# iot_hdmi_mux.net
KiCad netlist of a schematic drawn in Altium Designer
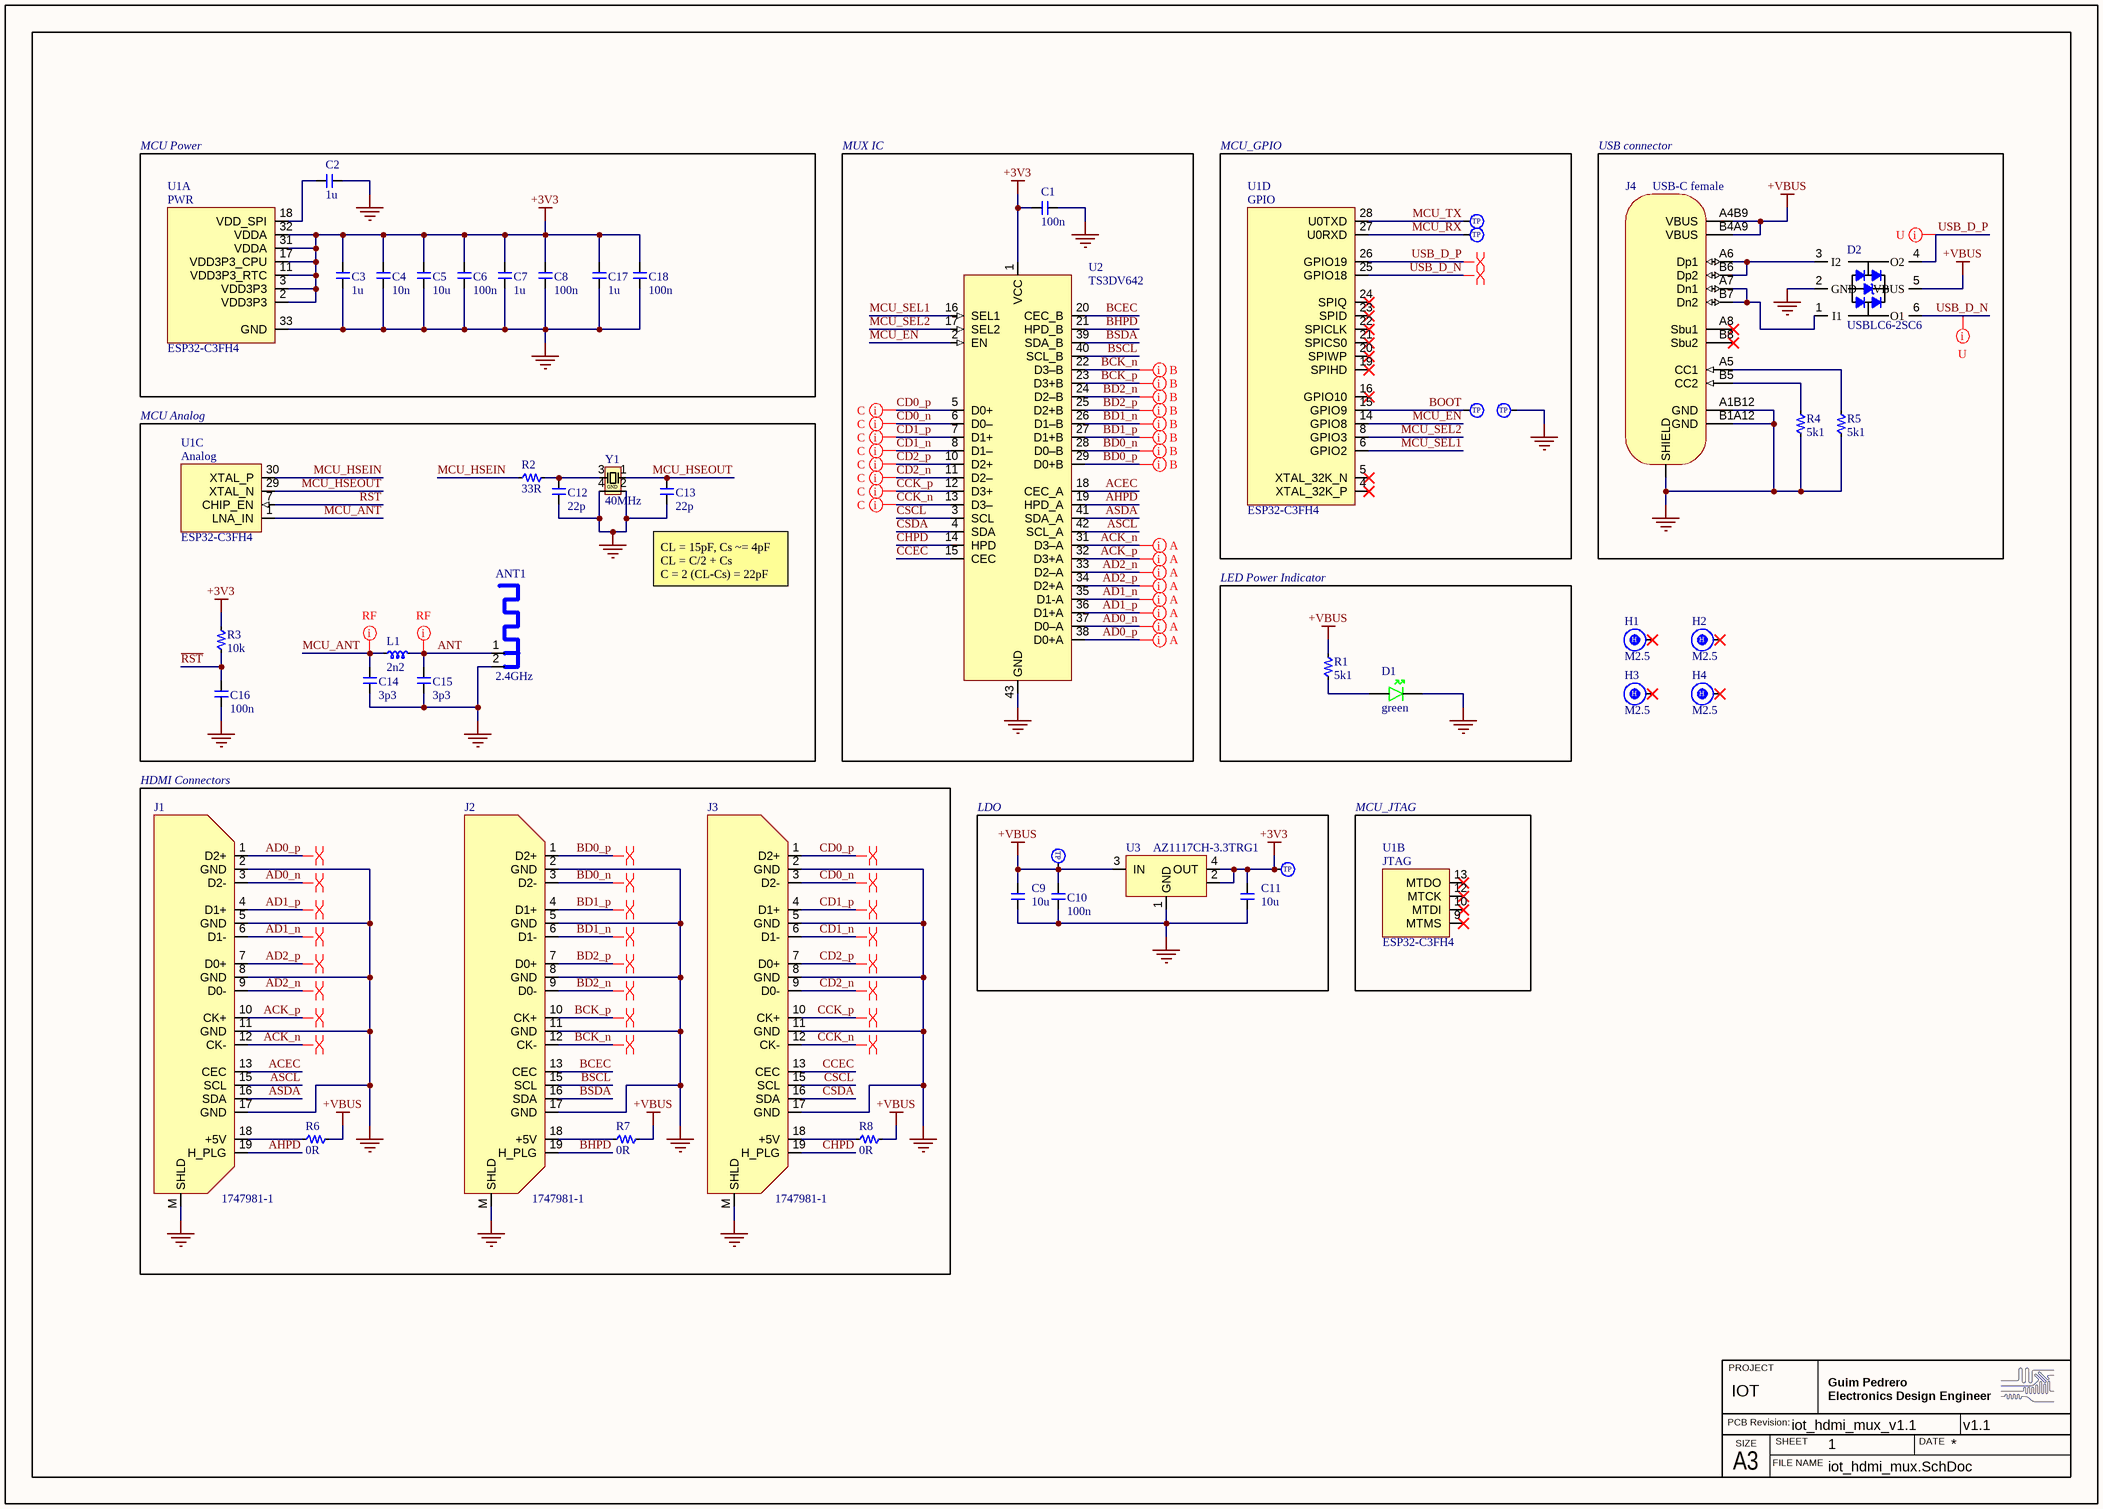
[diagram p0: iot_hdmi_mux.SchDoc]

(export (version "E")
  (design (tool "Eeschema 10.0.6"))
  (components
    (comp (ref "ANT1")
      (value "2.4GHz")
      (footprint "ANT_2.4")
      (description "SWRA117D 2.4GHz antenna design by TI")
      (libsource (lib "iot_hdmi_mux") (part "ANT_2.4"))
    )
    (comp (ref "C1")
      (value "100n")
      (footprint "C0402")
      (description "0402 cap")
      (libsource (lib "iot_hdmi_mux") (part "C_0402"))
    )
    (comp (ref "C2")
      (value "1u")
      (footprint "C0402")
      (description "0402 cap")
      (libsource (lib "LinearDriver") (part "C_0402"))
    )
    (comp (ref "C3")
      (value "1u")
      (footprint "C0402")
      (description "0402 cap")
      (libsource (lib "LinearDriver") (part "C_0402"))
    )
    (comp (ref "C4")
      (value "10n")
      (footprint "C0402")
      (description "0402 cap")
      (libsource (lib "iot_hdmi_mux") (part "C_0402"))
    )
    (comp (ref "C5")
      (value "10u")
      (footprint "C0402")
      (description "0402 cap")
      (libsource (lib "LinearDriver") (part "C_0402"))
    )
    (comp (ref "C6")
      (value "100n")
      (footprint "C0402")
      (description "0402 cap")
      (libsource (lib "iot_hdmi_mux") (part "C_0402"))
    )
    (comp (ref "C7")
      (value "1u")
      (footprint "C0402")
      (description "0402 cap")
      (libsource (lib "LinearDriver") (part "C_0402"))
    )
    (comp (ref "C8")
      (value "100n")
      (footprint "C0402")
      (description "0402 cap")
      (libsource (lib "iot_hdmi_mux") (part "C_0402"))
    )
    (comp (ref "C9")
      (value "10u")
      (footprint "C0402")
      (description "0402 cap")
      (libsource (lib "LinearDriver") (part "C_0402"))
    )
    (comp (ref "C10")
      (value "100n")
      (footprint "C0402")
      (description "0402 cap")
      (libsource (lib "iot_hdmi_mux") (part "C_0402"))
    )
    (comp (ref "C11")
      (value "10u")
      (footprint "C0402")
      (description "0402 cap")
      (libsource (lib "LinearDriver") (part "C_0402"))
    )
    (comp (ref "C12")
      (value "22p")
      (footprint "C0402")
      (description "0402 cap")
      (libsource (lib "FOC_Drive") (part "C_0402"))
    )
    (comp (ref "C13")
      (value "22p")
      (footprint "C0402")
      (description "0402 cap")
      (libsource (lib "FOC_Drive") (part "C_0402"))
    )
    (comp (ref "C14")
      (value "3p3")
      (footprint "C0402")
      (description "0402 cap")
      (libsource (lib "iot_hdmi_mux") (part "C_0402"))
    )
    (comp (ref "C15")
      (value "3p3")
      (footprint "C0402")
      (description "0402 cap")
      (libsource (lib "iot_hdmi_mux") (part "C_0402"))
    )
    (comp (ref "C16")
      (value "100n")
      (footprint "C0402")
      (description "0402 cap")
      (libsource (lib "iot_hdmi_mux") (part "C_0402"))
    )
    (comp (ref "C17")
      (value "1u")
      (footprint "C0402")
      (description "0402 cap")
      (libsource (lib "LinearDriver") (part "C_0402"))
    )
    (comp (ref "C18")
      (value "100n")
      (footprint "C0402")
      (description "0402 cap")
      (libsource (lib "iot_hdmi_mux") (part "C_0402"))
    )
    (comp (ref "D1")
      (value "green")
      (footprint "LED_0805_G")
      (description "0805 green LED")
      (libsource (lib "iot_hdmi_mux") (part "LED_0805_G"))
    )
    (comp (ref "D2")
      (value "USBLC6-2SC6")
      (footprint "USBLC6-2SC6")
      (description "Trans Voltage Suppressor Diode, 5V V(RWM), Unidirectional, 1 Element, Silicon")
      (fields (field (name "MANUFACTURER") "STMicroelectronics"))
      (libsource (lib "R20_PCBM") (part "USBLC6-2SC6"))
    )
    (comp (ref "H1")
      (value "M2.5")
      (footprint "M2.5_HOLE")
      (description "M2.5 hole with connection")
      (libsource (lib "iot_hdmi_mux") (part "M2.5_HOLE"))
    )
    (comp (ref "H2")
      (value "M2.5")
      (footprint "M2.5_HOLE")
      (description "M2.5 hole with connection")
      (libsource (lib "iot_hdmi_mux") (part "M2.5_HOLE"))
    )
    (comp (ref "H3")
      (value "M2.5")
      (footprint "M2.5_HOLE")
      (description "M2.5 hole with connection")
      (libsource (lib "iot_hdmi_mux") (part "M2.5_HOLE"))
    )
    (comp (ref "H4")
      (value "M2.5")
      (footprint "M2.5_HOLE")
      (description "M2.5 hole with connection")
      (libsource (lib "iot_hdmi_mux") (part "M2.5_HOLE"))
    )
    (comp (ref "J1")
      (value "1747981-1")
      (footprint "1747981-1")
      (description "HDMI (High-Definition Multimedia Interface) Connector; No Flange; Through hole")
      (fields (field (name "MANUFACTURER") "AMP - TE CONNECTIVITY"))
      (libsource (lib "iot_hdmi_mux") (part "1747981-1"))
    )
    (comp (ref "J2")
      (value "1747981-1")
      (footprint "1747981-1")
      (description "HDMI (High-Definition Multimedia Interface) Connector; No Flange; Through hole")
      (fields (field (name "MANUFACTURER") "AMP - TE CONNECTIVITY"))
      (libsource (lib "iot_hdmi_mux") (part "1747981-1"))
    )
    (comp (ref "J3")
      (value "1747981-1")
      (footprint "1747981-1")
      (description "HDMI (High-Definition Multimedia Interface) Connector; No Flange; Through hole")
      (fields (field (name "MANUFACTURER") "AMP - TE CONNECTIVITY"))
      (libsource (lib "iot_hdmi_mux") (part "1747981-1"))
    )
    (comp (ref "J4")
      (value "USB-C female")
      (footprint "TYPE-C-31-M-12")
      (description "Conn USB Type C PL 22 POS 0.5mm Solder ST SMD 22 Terminal 1Port Emboss T/R")
      (fields
        (field (name "MANUFACTURER") "HRO Electronics")
        (field (name "MANUFACTURER PART NUMBER") "TYPE-C-31-M-12")
      )
      (libsource (lib "rotor_magnetics_tb") (part "TYPE-C-31-M-12"))
    )
    (comp (ref "L1")
      (value "2n2")
      (footprint "L0402")
      (description "0402 inductor")
      (libsource (lib "iot_hdmi_mux") (part "L_0402"))
    )
    (comp (ref "R1")
      (value "5k1")
      (footprint "R0402")
      (description "0402 62.5mW")
      (libsource (lib "PCB_motor") (part "R_0402"))
    )
    (comp (ref "R2")
      (value "33R")
      (footprint "R0402")
      (description "0402 62.5mW")
      (libsource (lib "iot_hdmi_mux") (part "R_0402"))
    )
    (comp (ref "R3")
      (value "10k")
      (footprint "R0402")
      (description "0402 62.5mW")
      (libsource (lib "iot_hdmi_mux") (part "R_0402"))
    )
    (comp (ref "R4")
      (value "5k1")
      (footprint "R0402")
      (description "0402 62.5mW")
      (libsource (lib "PCB_motor") (part "R_0402"))
    )
    (comp (ref "R5")
      (value "5k1")
      (footprint "R0402")
      (description "0402 62.5mW")
      (libsource (lib "PCB_motor") (part "R_0402"))
    )
    (comp (ref "R6")
      (value "0R")
      (footprint "R0402")
      (description "0402 62.5mW")
      (libsource (lib "iot_hdmi_mux") (part "R_0402"))
    )
    (comp (ref "R7")
      (value "0R")
      (footprint "R0402")
      (description "0402 62.5mW")
      (libsource (lib "iot_hdmi_mux") (part "R_0402"))
    )
    (comp (ref "R8")
      (value "0R")
      (footprint "R0402")
      (description "0402 62.5mW")
      (libsource (lib "iot_hdmi_mux") (part "R_0402"))
    )
    (comp (ref "TP1")
      (value "Testing_Point_1mm")
      (footprint "TestingPoint_1mm")
      (description "1mm testing point")
      (libsource (lib "iot_hdmi_mux") (part "Testing_Point_1mm"))
    )
    (comp (ref "TP2")
      (value "Testing_Point_1mm")
      (footprint "TestingPoint_1mm")
      (description "1mm testing point")
      (libsource (lib "iot_hdmi_mux") (part "Testing_Point_1mm"))
    )
    (comp (ref "TP3")
      (value "Testing_Point_1mm")
      (footprint "TestingPoint_1mm")
      (description "1mm testing point")
      (libsource (lib "iot_hdmi_mux") (part "Testing_Point_1mm"))
    )
    (comp (ref "TP4")
      (value "Testing_Point_1mm")
      (footprint "TestingPoint_1mm")
      (description "1mm testing point")
      (libsource (lib "iot_hdmi_mux") (part "Testing_Point_1mm"))
    )
    (comp (ref "TP5")
      (value "Testing_Point_1mm")
      (footprint "TestingPoint_1mm")
      (description "1mm testing point")
      (libsource (lib "LinearDriver") (part "Testing_Point_1mm"))
    )
    (comp (ref "TP6")
      (value "Testing_Point_1mm")
      (footprint "TestingPoint_1mm")
      (description "1mm testing point")
      (libsource (lib "LinearDriver") (part "Testing_Point_1mm"))
    )
    (comp (ref "U1")
      (value "ESP32-C3FH4")
      (footprint "QFN50P500X500X90_HS-33N")
      (fields (field (name "MANUFACTURER") "Espressif Systems"))
      (libsource (lib "") (part "ESP32-C3FH4_1"))
    )
    (comp (ref "U2")
      (value "TS3DV642")
      (footprint "QFN50P350X900X80_HS-43N")
      (description "6-Gbps 12-channel differential 1-to-2 and 2-to-1 mux for DVI 1.0/ DisplayPort 1.4 /HDMI 2.0")
      (fields
        (field (name "MANUFACTURER") "Texas Instruments")
        (field (name "MANUFACTURER PART NUMBER") "TS3DV642A0RUAR")
      )
      (libsource (lib "iot_hdmi_mux") (part "TS3DV642"))
    )
    (comp (ref "U3")
      (value "AZ1117CH-3.3TRG1")
      (footprint "AZ1117CH-3.3TRG1")
      (description "Fixed Positive LDO Regulator, 3.3V, 1.3V Dropout, BIPolar, PDSO3")
      (fields (field (name "MANUFACTURER") "Diodes"))
      (libsource (lib "LinearDriver") (part "AZ1117CH-3.3TRG1"))
    )
    (comp (ref "Y1")
      (value "40MHz")
      (footprint "SMD3225-4P")
      (description "40MHz Surface Mount Crystal 15pF ±10ppm ±20ppm SMD3225-4P Crystals ROHS")
      (libsource (lib "iot_hdmi_mux") (part "X322540MPB4SI"))
    )
  )
  (nets
    (net (code "1") (name "+3V3") (class "Default")
      (node (ref "C1") (pin "2") (pinfunction "2_2") (pintype "passive"))
      (node (ref "C11") (pin "2") (pinfunction "2_2") (pintype "passive"))
      (node (ref "C17") (pin "2") (pinfunction "2_2") (pintype "passive"))
      (node (ref "C18") (pin "1") (pinfunction "1_1") (pintype "passive"))
      (node (ref "C3") (pin "2") (pinfunction "2_2") (pintype "passive"))
      (node (ref "C4") (pin "1") (pinfunction "1_1") (pintype "passive"))
      (node (ref "C5") (pin "2") (pinfunction "2_2") (pintype "passive"))
      (node (ref "C6") (pin "1") (pinfunction "1_1") (pintype "passive"))
      (node (ref "C7") (pin "2") (pinfunction "2_2") (pintype "passive"))
      (node (ref "C8") (pin "1") (pinfunction "1_1") (pintype "passive"))
      (node (ref "R3") (pin "2") (pinfunction "2_2") (pintype "passive"))
      (node (ref "TP6") (pin "1") (pinfunction "1_1") (pintype "passive"))
      (node (ref "U1") (pin "11") (pinfunction "VDD3P3_RTC_11") (pintype "power_in"))
      (node (ref "U1") (pin "17") (pinfunction "VDD3P3_CPU_17") (pintype "power_in"))
      (node (ref "U1") (pin "2") (pinfunction "VDD3P3_2") (pintype "power_in"))
      (node (ref "U1") (pin "3") (pinfunction "VDD3P3_3") (pintype "power_in"))
      (node (ref "U1") (pin "31") (pinfunction "VDDA_31") (pintype "power_in"))
      (node (ref "U1") (pin "32") (pinfunction "VDDA_32") (pintype "power_in"))
      (node (ref "U2") (pin "1") (pinfunction "VCC_1") (pintype "power_in"))
      (node (ref "U3") (pin "2") (pinfunction "OUT_2") (pintype "power_in"))
      (node (ref "U3") (pin "4") (pinfunction "OUT_4") (pintype "power_in"))
    )
    (net (code "2") (name "+VBUS") (class "Default")
      (node (ref "C10") (pin "1") (pinfunction "1_1") (pintype "passive"))
      (node (ref "C9") (pin "2") (pinfunction "2_2") (pintype "passive"))
      (node (ref "D2") (pin "5") (pinfunction "VBUS_5") (pintype "passive"))
      (node (ref "J4") (pin "A4B9") (pinfunction "VBUS_A4B9") (pintype "power_in"))
      (node (ref "J4") (pin "B4A9") (pinfunction "VBUS_B4A9") (pintype "power_in"))
      (node (ref "R1") (pin "2") (pinfunction "2_2") (pintype "passive"))
      (node (ref "R6") (pin "1") (pinfunction "1_1") (pintype "passive"))
      (node (ref "R7") (pin "1") (pinfunction "1_1") (pintype "passive"))
      (node (ref "R8") (pin "1") (pinfunction "1_1") (pintype "passive"))
      (node (ref "TP5") (pin "1") (pinfunction "1_1") (pintype "passive"))
      (node (ref "U3") (pin "3") (pinfunction "IN_3") (pintype "power_in"))
    )
    (net (code "3") (name "/ACEC") (class "Default")
      (node (ref "J1") (pin "13") (pinfunction "CEC_13") (pintype "bidirectional"))
      (node (ref "U2") (pin "18") (pinfunction "CEC_A_18") (pintype "bidirectional"))
    )
    (net (code "4") (name "/ACK_n") (class "Default")
      (node (ref "J1") (pin "12") (pinfunction "CK-_12") (pintype "bidirectional"))
      (node (ref "U2") (pin "31") (pinfunction "D3–A_31") (pintype "bidirectional"))
    )
    (net (code "5") (name "/ACK_p") (class "Default")
      (node (ref "J1") (pin "10") (pinfunction "CK+_10") (pintype "bidirectional"))
      (node (ref "U2") (pin "32") (pinfunction "D3+A_32") (pintype "bidirectional"))
    )
    (net (code "6") (name "/AD0_n") (class "Default")
      (node (ref "J1") (pin "3") (pinfunction "D2-_3") (pintype "bidirectional"))
      (node (ref "U2") (pin "37") (pinfunction "D0–A_37") (pintype "bidirectional"))
    )
    (net (code "7") (name "/AD0_p") (class "Default")
      (node (ref "J1") (pin "1") (pinfunction "D2+_1") (pintype "bidirectional"))
      (node (ref "U2") (pin "38") (pinfunction "D0+A_38") (pintype "bidirectional"))
    )
    (net (code "8") (name "/AD1_n") (class "Default")
      (node (ref "J1") (pin "6") (pinfunction "D1-_6") (pintype "bidirectional"))
      (node (ref "U2") (pin "35") (pinfunction "D1-A_35") (pintype "bidirectional"))
    )
    (net (code "9") (name "/AD1_p") (class "Default")
      (node (ref "J1") (pin "4") (pinfunction "D1+_4") (pintype "bidirectional"))
      (node (ref "U2") (pin "36") (pinfunction "D1+A_36") (pintype "bidirectional"))
    )
    (net (code "10") (name "/AD2_n") (class "Default")
      (node (ref "J1") (pin "9") (pinfunction "D0-_9") (pintype "bidirectional"))
      (node (ref "U2") (pin "33") (pinfunction "D2–A_33") (pintype "bidirectional"))
    )
    (net (code "11") (name "/AD2_p") (class "Default")
      (node (ref "J1") (pin "7") (pinfunction "D0+_7") (pintype "bidirectional"))
      (node (ref "U2") (pin "34") (pinfunction "D2+A_34") (pintype "bidirectional"))
    )
    (net (code "12") (name "/AHPD") (class "Default")
      (node (ref "J1") (pin "19") (pinfunction "H_PLG_19") (pintype "bidirectional"))
      (node (ref "U2") (pin "19") (pinfunction "HPD_A_19") (pintype "bidirectional"))
    )
    (net (code "13") (name "/ANT") (class "Default")
      (node (ref "ANT1") (pin "1") (pinfunction "1_1") (pintype "passive"))
      (node (ref "C15") (pin "1") (pinfunction "1_1") (pintype "passive"))
      (node (ref "L1") (pin "2") (pinfunction "2_2") (pintype "passive"))
    )
    (net (code "14") (name "/ASCL") (class "Default")
      (node (ref "J1") (pin "15") (pinfunction "SCL_15") (pintype "bidirectional"))
      (node (ref "U2") (pin "42") (pinfunction "SCL_A_42") (pintype "bidirectional"))
    )
    (net (code "15") (name "/ASDA") (class "Default")
      (node (ref "J1") (pin "16") (pinfunction "SDA_16") (pintype "bidirectional"))
      (node (ref "U2") (pin "41") (pinfunction "SDA_A_41") (pintype "bidirectional"))
    )
    (net (code "16") (name "/BCEC") (class "Default")
      (node (ref "J2") (pin "13") (pinfunction "CEC_13") (pintype "bidirectional"))
      (node (ref "U2") (pin "20") (pinfunction "CEC_B_20") (pintype "bidirectional"))
    )
    (net (code "17") (name "/BCK_n") (class "Default")
      (node (ref "J2") (pin "12") (pinfunction "CK-_12") (pintype "bidirectional"))
      (node (ref "U2") (pin "22") (pinfunction "D3–B_22") (pintype "bidirectional"))
    )
    (net (code "18") (name "/BCK_p") (class "Default")
      (node (ref "J2") (pin "10") (pinfunction "CK+_10") (pintype "bidirectional"))
      (node (ref "U2") (pin "23") (pinfunction "D3+B_23") (pintype "bidirectional"))
    )
    (net (code "19") (name "/BD0_n") (class "Default")
      (node (ref "J2") (pin "3") (pinfunction "D2-_3") (pintype "bidirectional"))
      (node (ref "U2") (pin "28") (pinfunction "D0–B_28") (pintype "bidirectional"))
    )
    (net (code "20") (name "/BD0_p") (class "Default")
      (node (ref "J2") (pin "1") (pinfunction "D2+_1") (pintype "bidirectional"))
      (node (ref "U2") (pin "29") (pinfunction "D0+B_29") (pintype "bidirectional"))
    )
    (net (code "21") (name "/BD1_n") (class "Default")
      (node (ref "J2") (pin "6") (pinfunction "D1-_6") (pintype "bidirectional"))
      (node (ref "U2") (pin "26") (pinfunction "D1–B_26") (pintype "bidirectional"))
    )
    (net (code "22") (name "/BD1_p") (class "Default")
      (node (ref "J2") (pin "4") (pinfunction "D1+_4") (pintype "bidirectional"))
      (node (ref "U2") (pin "27") (pinfunction "D1+B_27") (pintype "bidirectional"))
    )
    (net (code "23") (name "/BD2_n") (class "Default")
      (node (ref "J2") (pin "9") (pinfunction "D0-_9") (pintype "bidirectional"))
      (node (ref "U2") (pin "24") (pinfunction "D2–B_24") (pintype "bidirectional"))
    )
    (net (code "24") (name "/BD2_p") (class "Default")
      (node (ref "J2") (pin "7") (pinfunction "D0+_7") (pintype "bidirectional"))
      (node (ref "U2") (pin "25") (pinfunction "D2+B_25") (pintype "bidirectional"))
    )
    (net (code "25") (name "/BHPD") (class "Default")
      (node (ref "J2") (pin "19") (pinfunction "H_PLG_19") (pintype "bidirectional"))
      (node (ref "U2") (pin "21") (pinfunction "HPD_B_21") (pintype "bidirectional"))
    )
    (net (code "26") (name "/BOOT") (class "Default")
      (node (ref "TP3") (pin "1") (pinfunction "1_1") (pintype "passive"))
      (node (ref "U1") (pin "15") (pinfunction "GPIO9_15") (pintype "bidirectional"))
    )
    (net (code "27") (name "/BSCL") (class "Default")
      (node (ref "J2") (pin "15") (pinfunction "SCL_15") (pintype "bidirectional"))
      (node (ref "U2") (pin "40") (pinfunction "SCL_B_40") (pintype "bidirectional"))
    )
    (net (code "28") (name "/BSDA") (class "Default")
      (node (ref "J2") (pin "16") (pinfunction "SDA_16") (pintype "bidirectional"))
      (node (ref "U2") (pin "39") (pinfunction "SDA_B_39") (pintype "bidirectional"))
    )
    (net (code "29") (name "/CCEC") (class "Default")
      (node (ref "J3") (pin "13") (pinfunction "CEC_13") (pintype "bidirectional"))
      (node (ref "U2") (pin "15") (pinfunction "CEC_15") (pintype "bidirectional"))
    )
    (net (code "30") (name "/CCK_n") (class "Default")
      (node (ref "J3") (pin "12") (pinfunction "CK-_12") (pintype "bidirectional"))
      (node (ref "U2") (pin "13") (pinfunction "D3–_13") (pintype "bidirectional"))
    )
    (net (code "31") (name "/CCK_p") (class "Default")
      (node (ref "J3") (pin "10") (pinfunction "CK+_10") (pintype "bidirectional"))
      (node (ref "U2") (pin "12") (pinfunction "D3+_12") (pintype "bidirectional"))
    )
    (net (code "32") (name "/CD0_n") (class "Default")
      (node (ref "J3") (pin "3") (pinfunction "D2-_3") (pintype "bidirectional"))
      (node (ref "U2") (pin "6") (pinfunction "D0–_6") (pintype "bidirectional"))
    )
    (net (code "33") (name "/CD0_p") (class "Default")
      (node (ref "J3") (pin "1") (pinfunction "D2+_1") (pintype "bidirectional"))
      (node (ref "U2") (pin "5") (pinfunction "D0+_5") (pintype "bidirectional"))
    )
    (net (code "34") (name "/CD1_n") (class "Default")
      (node (ref "J3") (pin "6") (pinfunction "D1-_6") (pintype "bidirectional"))
      (node (ref "U2") (pin "8") (pinfunction "D1–_8") (pintype "bidirectional"))
    )
    (net (code "35") (name "/CD1_p") (class "Default")
      (node (ref "J3") (pin "4") (pinfunction "D1+_4") (pintype "bidirectional"))
      (node (ref "U2") (pin "7") (pinfunction "D1+_7") (pintype "bidirectional"))
    )
    (net (code "36") (name "/CD2_n") (class "Default")
      (node (ref "J3") (pin "9") (pinfunction "D0-_9") (pintype "bidirectional"))
      (node (ref "U2") (pin "11") (pinfunction "D2–_11") (pintype "bidirectional"))
    )
    (net (code "37") (name "/CD2_p") (class "Default")
      (node (ref "J3") (pin "7") (pinfunction "D0+_7") (pintype "bidirectional"))
      (node (ref "U2") (pin "10") (pinfunction "D2+_10") (pintype "bidirectional"))
    )
    (net (code "38") (name "/CHPD") (class "Default")
      (node (ref "J3") (pin "19") (pinfunction "H_PLG_19") (pintype "bidirectional"))
      (node (ref "U2") (pin "14") (pinfunction "HPD_14") (pintype "bidirectional"))
    )
    (net (code "39") (name "/CSCL") (class "Default")
      (node (ref "J3") (pin "15") (pinfunction "SCL_15") (pintype "bidirectional"))
      (node (ref "U2") (pin "3") (pinfunction "SCL_3") (pintype "bidirectional"))
    )
    (net (code "40") (name "/CSDA") (class "Default")
      (node (ref "J3") (pin "16") (pinfunction "SDA_16") (pintype "bidirectional"))
      (node (ref "U2") (pin "4") (pinfunction "SDA_4") (pintype "bidirectional"))
    )
    (net (code "41") (name "/MCU_ANT") (class "Default")
      (node (ref "C14") (pin "1") (pinfunction "1_1") (pintype "passive"))
      (node (ref "L1") (pin "1") (pinfunction "1_1") (pintype "passive"))
      (node (ref "U1") (pin "1") (pinfunction "LNA_IN_1") (pintype "bidirectional"))
    )
    (net (code "42") (name "/MCU_EN") (class "Default")
      (node (ref "U1") (pin "14") (pinfunction "GPIO8_14") (pintype "bidirectional"))
      (node (ref "U2") (pin "2") (pinfunction "EN_2") (pintype "input"))
    )
    (net (code "43") (name "/MCU_HSEIN") (class "Default")
      (node (ref "R2") (pin "1") (pinfunction "1_1") (pintype "passive"))
      (node (ref "U1") (pin "30") (pinfunction "XTAL_P_30") (pintype "bidirectional"))
    )
    (net (code "44") (name "/MCU_HSEOUT") (class "Default")
      (node (ref "C13") (pin "2") (pinfunction "2_2") (pintype "passive"))
      (node (ref "U1") (pin "29") (pinfunction "XTAL_N_29") (pintype "bidirectional"))
      (node (ref "Y1") (pin "1") (pinfunction "1_1") (pintype "passive"))
    )
    (net (code "45") (name "/MCU_RX") (class "Default")
      (node (ref "TP2") (pin "1") (pinfunction "1_1") (pintype "passive"))
      (node (ref "U1") (pin "27") (pinfunction "U0RXD_27") (pintype "bidirectional"))
    )
    (net (code "46") (name "/MCU_SEL1") (class "Default")
      (node (ref "U1") (pin "6") (pinfunction "GPIO2_6") (pintype "bidirectional"))
      (node (ref "U2") (pin "16") (pinfunction "SEL1_16") (pintype "input"))
    )
    (net (code "47") (name "/MCU_SEL2") (class "Default")
      (node (ref "U1") (pin "8") (pinfunction "GPIO3_8") (pintype "bidirectional"))
      (node (ref "U2") (pin "17") (pinfunction "SEL2_17") (pintype "input"))
    )
    (net (code "48") (name "/MCU_TX") (class "Default")
      (node (ref "TP1") (pin "1") (pinfunction "1_1") (pintype "passive"))
      (node (ref "U1") (pin "28") (pinfunction "U0TXD_28") (pintype "bidirectional"))
    )
    (net (code "49") (name "/USB_D_N") (class "Default")
      (node (ref "D2") (pin "6") (pinfunction "O1_6") (pintype "passive"))
      (node (ref "U1") (pin "25") (pinfunction "GPIO18_25") (pintype "bidirectional"))
    )
    (net (code "50") (name "/USB_D_P") (class "Default")
      (node (ref "D2") (pin "4") (pinfunction "O2_4") (pintype "passive"))
      (node (ref "U1") (pin "26") (pinfunction "GPIO19_26") (pintype "bidirectional"))
    )
    (net (code "51") (name "/~{RST}") (class "Default")
      (node (ref "C16") (pin "1") (pinfunction "1_1") (pintype "passive"))
      (node (ref "R3") (pin "1") (pinfunction "1_1") (pintype "passive"))
      (node (ref "U1") (pin "7") (pinfunction "CHIP_EN_7") (pintype "input"))
    )
    (net (code "52") (name "GND") (class "Default")
      (node (ref "ANT1") (pin "2") (pinfunction "2_2") (pintype "passive"))
      (node (ref "C1") (pin "1") (pinfunction "1_1") (pintype "passive"))
      (node (ref "C10") (pin "2") (pinfunction "2_2") (pintype "passive"))
      (node (ref "C11") (pin "1") (pinfunction "1_1") (pintype "passive"))
      (node (ref "C12") (pin "1") (pinfunction "1_1") (pintype "passive"))
      (node (ref "C13") (pin "1") (pinfunction "1_1") (pintype "passive"))
      (node (ref "C14") (pin "2") (pinfunction "2_2") (pintype "passive"))
      (node (ref "C15") (pin "2") (pinfunction "2_2") (pintype "passive"))
      (node (ref "C16") (pin "2") (pinfunction "2_2") (pintype "passive"))
      (node (ref "C17") (pin "1") (pinfunction "1_1") (pintype "passive"))
      (node (ref "C18") (pin "2") (pinfunction "2_2") (pintype "passive"))
      (node (ref "C2") (pin "2") (pinfunction "2_2") (pintype "passive"))
      (node (ref "C3") (pin "1") (pinfunction "1_1") (pintype "passive"))
      (node (ref "C4") (pin "2") (pinfunction "2_2") (pintype "passive"))
      (node (ref "C5") (pin "1") (pinfunction "1_1") (pintype "passive"))
      (node (ref "C6") (pin "2") (pinfunction "2_2") (pintype "passive"))
      (node (ref "C7") (pin "1") (pinfunction "1_1") (pintype "passive"))
      (node (ref "C8") (pin "2") (pinfunction "2_2") (pintype "passive"))
      (node (ref "C9") (pin "1") (pinfunction "1_1") (pintype "passive"))
      (node (ref "D1") (pin "1") (pinfunction "1_1") (pintype "passive"))
      (node (ref "D2") (pin "2") (pinfunction "GND_2") (pintype "passive"))
      (node (ref "J1") (pin "11") (pinfunction "GND_11") (pintype "power_in"))
      (node (ref "J1") (pin "17") (pinfunction "GND_17") (pintype "power_in"))
      (node (ref "J1") (pin "2") (pinfunction "GND_2") (pintype "power_in"))
      (node (ref "J1") (pin "5") (pinfunction "GND_5") (pintype "power_in"))
      (node (ref "J1") (pin "8") (pinfunction "GND_8") (pintype "power_in"))
      (node (ref "J1") (pin "M") (pinfunction "SHLD_M") (pintype "power_in"))
      (node (ref "J2") (pin "11") (pinfunction "GND_11") (pintype "power_in"))
      (node (ref "J2") (pin "17") (pinfunction "GND_17") (pintype "power_in"))
      (node (ref "J2") (pin "2") (pinfunction "GND_2") (pintype "power_in"))
      (node (ref "J2") (pin "5") (pinfunction "GND_5") (pintype "power_in"))
      (node (ref "J2") (pin "8") (pinfunction "GND_8") (pintype "power_in"))
      (node (ref "J2") (pin "M") (pinfunction "SHLD_M") (pintype "power_in"))
      (node (ref "J3") (pin "11") (pinfunction "GND_11") (pintype "power_in"))
      (node (ref "J3") (pin "17") (pinfunction "GND_17") (pintype "power_in"))
      (node (ref "J3") (pin "2") (pinfunction "GND_2") (pintype "power_in"))
      (node (ref "J3") (pin "5") (pinfunction "GND_5") (pintype "power_in"))
      (node (ref "J3") (pin "8") (pinfunction "GND_8") (pintype "power_in"))
      (node (ref "J3") (pin "M") (pinfunction "SHLD_M") (pintype "power_in"))
      (node (ref "J4") (pin "A1B12") (pinfunction "GND_A1B12") (pintype "power_in"))
      (node (ref "J4") (pin "B1A12") (pinfunction "GND_B1A12") (pintype "power_in"))
      (node (ref "J4") (pin "M1") (pinfunction "SHIELD_M1") (pintype "passive"))
      (node (ref "R4") (pin "1") (pinfunction "1_1") (pintype "passive"))
      (node (ref "R5") (pin "1") (pinfunction "1_1") (pintype "passive"))
      (node (ref "TP4") (pin "1") (pinfunction "1_1") (pintype "passive"))
      (node (ref "U1") (pin "33") (pinfunction "GND_33") (pintype "power_in"))
      (node (ref "U2") (pin "43") (pinfunction "GND_43") (pintype "power_in"))
      (node (ref "U3") (pin "1") (pinfunction "GND_1") (pintype "power_in"))
      (node (ref "Y1") (pin "2") (pinfunction "2_2") (pintype "passive"))
      (node (ref "Y1") (pin "4") (pinfunction "4_4") (pintype "passive"))
    )
    (net (code "53") (name "Net-(C12-Pad2)") (class "Default")
      (node (ref "C12") (pin "2") (pinfunction "2_2") (pintype "passive"))
      (node (ref "R2") (pin "2") (pinfunction "2_2") (pintype "passive"))
      (node (ref "Y1") (pin "3") (pinfunction "3_3") (pintype "passive"))
    )
    (net (code "54") (name "Net-(D1-Pad2)") (class "Default")
      (node (ref "D1") (pin "2") (pinfunction "2_2") (pintype "passive"))
      (node (ref "R1") (pin "1") (pinfunction "1_1") (pintype "passive"))
    )
    (net (code "55") (name "Net-(D2-I1)") (class "Default")
      (node (ref "D2") (pin "1") (pinfunction "I1_1") (pintype "passive"))
      (node (ref "J4") (pin "A7") (pinfunction "Dn1_A7") (pintype "bidirectional"))
      (node (ref "J4") (pin "B7") (pinfunction "Dn2_B7") (pintype "bidirectional"))
    )
    (net (code "56") (name "Net-(D2-I2)") (class "Default")
      (node (ref "D2") (pin "3") (pinfunction "I2_3") (pintype "passive"))
      (node (ref "J4") (pin "A6") (pinfunction "Dp1_A6") (pintype "bidirectional"))
      (node (ref "J4") (pin "B6") (pinfunction "Dp2_B6") (pintype "bidirectional"))
    )
    (net (code "57") (name "Net-(J1-+5V)") (class "Default")
      (node (ref "J1") (pin "18") (pinfunction "+5V_18") (pintype "power_in"))
      (node (ref "R6") (pin "2") (pinfunction "2_2") (pintype "passive"))
    )
    (net (code "58") (name "Net-(J2-+5V)") (class "Default")
      (node (ref "J2") (pin "18") (pinfunction "+5V_18") (pintype "power_in"))
      (node (ref "R7") (pin "2") (pinfunction "2_2") (pintype "passive"))
    )
    (net (code "59") (name "Net-(J3-+5V)") (class "Default")
      (node (ref "J3") (pin "18") (pinfunction "+5V_18") (pintype "power_in"))
      (node (ref "R8") (pin "2") (pinfunction "2_2") (pintype "passive"))
    )
    (net (code "60") (name "Net-(J4-CC1)") (class "Default")
      (node (ref "J4") (pin "A5") (pinfunction "CC1_A5") (pintype "input"))
      (node (ref "R5") (pin "2") (pinfunction "2_2") (pintype "passive"))
    )
    (net (code "61") (name "Net-(J4-CC2)") (class "Default")
      (node (ref "J4") (pin "B5") (pinfunction "CC2_B5") (pintype "input"))
      (node (ref "R4") (pin "2") (pinfunction "2_2") (pintype "passive"))
    )
    (net (code "62") (name "Net-(U1A-VDD_SPI)") (class "Default")
      (node (ref "C2") (pin "1") (pinfunction "1_1") (pintype "passive"))
      (node (ref "U1") (pin "18") (pinfunction "VDD_SPI_18") (pintype "power_in"))
    )
    (net (code "63") (name "unconnected-(H1-Pad1)") (class "Default")
      (node (ref "H1") (pin "1") (pinfunction "1_1") (pintype "passive+no_connect"))
    )
    (net (code "64") (name "unconnected-(H2-Pad1)") (class "Default")
      (node (ref "H2") (pin "1") (pinfunction "1_1") (pintype "passive+no_connect"))
    )
    (net (code "65") (name "unconnected-(H3-Pad1)") (class "Default")
      (node (ref "H3") (pin "1") (pinfunction "1_1") (pintype "passive+no_connect"))
    )
    (net (code "66") (name "unconnected-(H4-Pad1)") (class "Default")
      (node (ref "H4") (pin "1") (pinfunction "1_1") (pintype "passive+no_connect"))
    )
    (net (code "67") (name "unconnected-(J4-Sbu1-PadA8)") (class "Default")
      (node (ref "J4") (pin "A8") (pinfunction "Sbu1_A8") (pintype "passive+no_connect"))
    )
    (net (code "68") (name "unconnected-(J4-Sbu2-PadB8)") (class "Default")
      (node (ref "J4") (pin "B8") (pinfunction "Sbu2_B8") (pintype "passive+no_connect"))
    )
    (net (code "69") (name "unconnected-(U1B-MTCK-Pad12)") (class "Default")
      (node (ref "U1") (pin "12") (pinfunction "MTCK_12") (pintype "bidirectional+no_connect"))
    )
    (net (code "70") (name "unconnected-(U1B-MTDI-Pad10)") (class "Default")
      (node (ref "U1") (pin "10") (pinfunction "MTDI_10") (pintype "bidirectional+no_connect"))
    )
    (net (code "71") (name "unconnected-(U1B-MTDO-Pad13)") (class "Default")
      (node (ref "U1") (pin "13") (pinfunction "MTDO_13") (pintype "bidirectional+no_connect"))
    )
    (net (code "72") (name "unconnected-(U1B-MTMS-Pad9)") (class "Default")
      (node (ref "U1") (pin "9") (pinfunction "MTMS_9") (pintype "bidirectional+no_connect"))
    )
    (net (code "73") (name "unconnected-(U1D-GPIO10-Pad16)") (class "Default")
      (node (ref "U1") (pin "16") (pinfunction "GPIO10_16") (pintype "bidirectional+no_connect"))
    )
    (net (code "74") (name "unconnected-(U1D-SPICLK-Pad22)") (class "Default")
      (node (ref "U1") (pin "22") (pinfunction "SPICLK_22") (pintype "bidirectional+no_connect"))
    )
    (net (code "75") (name "unconnected-(U1D-SPICS0-Pad21)") (class "Default")
      (node (ref "U1") (pin "21") (pinfunction "SPICS0_21") (pintype "bidirectional+no_connect"))
    )
    (net (code "76") (name "unconnected-(U1D-SPID-Pad23)") (class "Default")
      (node (ref "U1") (pin "23") (pinfunction "SPID_23") (pintype "bidirectional+no_connect"))
    )
    (net (code "77") (name "unconnected-(U1D-SPIHD-Pad19)") (class "Default")
      (node (ref "U1") (pin "19") (pinfunction "SPIHD_19") (pintype "bidirectional+no_connect"))
    )
    (net (code "78") (name "unconnected-(U1D-SPIQ-Pad24)") (class "Default")
      (node (ref "U1") (pin "24") (pinfunction "SPIQ_24") (pintype "bidirectional+no_connect"))
    )
    (net (code "79") (name "unconnected-(U1D-SPIWP-Pad20)") (class "Default")
      (node (ref "U1") (pin "20") (pinfunction "SPIWP_20") (pintype "bidirectional+no_connect"))
    )
    (net (code "80") (name "unconnected-(U1D-XTAL_32K_N-Pad5)") (class "Default")
      (node (ref "U1") (pin "5") (pinfunction "XTAL_32K_N_5") (pintype "bidirectional+no_connect"))
    )
    (net (code "81") (name "unconnected-(U1D-XTAL_32K_P-Pad4)") (class "Default")
      (node (ref "U1") (pin "4") (pinfunction "XTAL_32K_P_4") (pintype "bidirectional+no_connect"))
    )
  )
)
